# qo-100-digital-power-meter.net
KiCad netlist of a schematic drawn in EAGLE
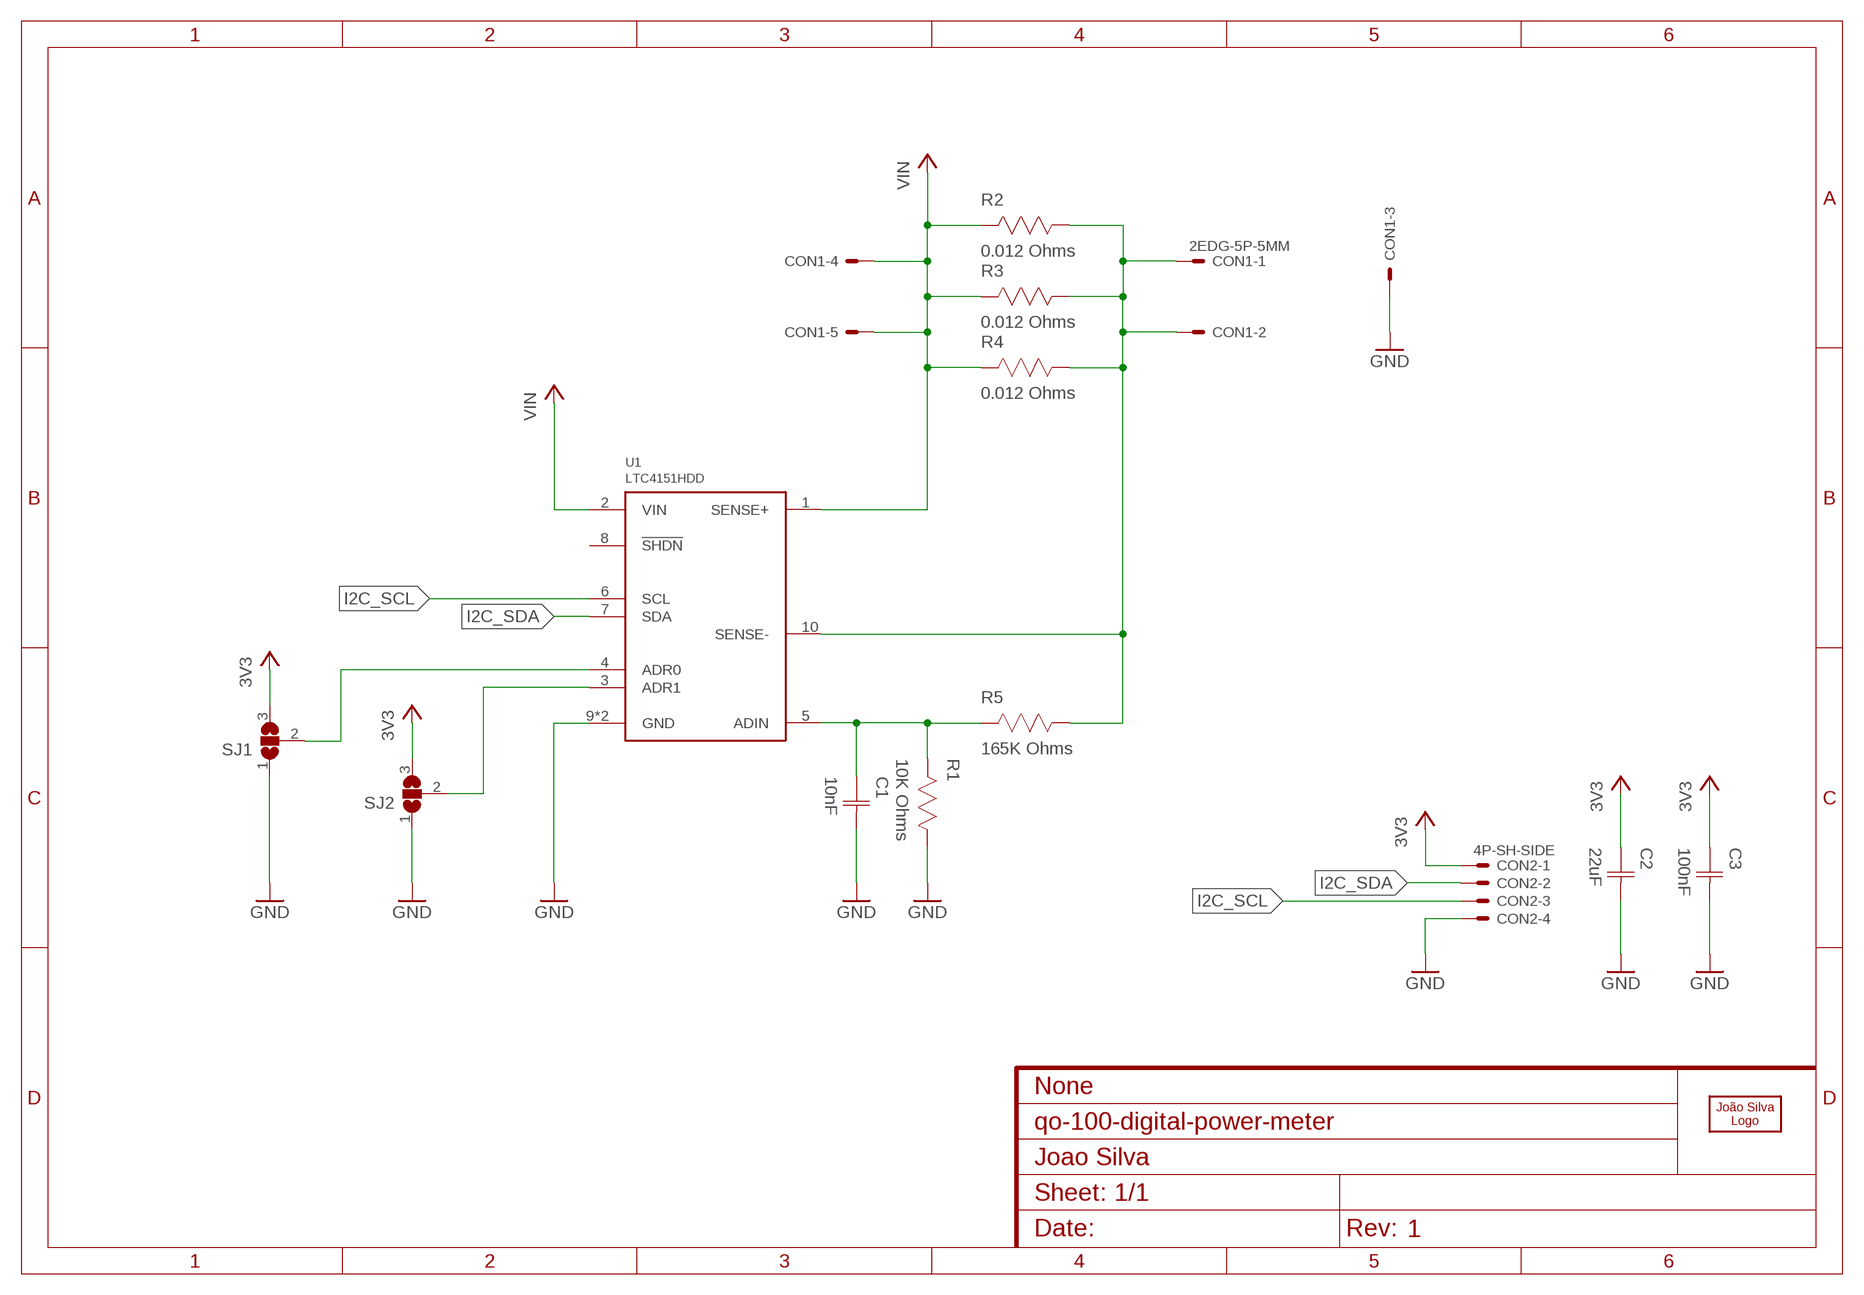
[diagram p0: schematic, sheet 1]

(export (version "E")
  (design (tool "Eeschema 10.0.6"))
  (components
    (comp (ref "C1")
      (value "10nF")
      (footprint "eagle-import:CAP0603")
      (libsource (lib "eagle-import") (part "CAPACITOR-0603"))
    )
    (comp (ref "C2")
      (value "22uF")
      (footprint "eagle-import:CAP1206")
      (libsource (lib "eagle-import") (part "CAPACITOR-1206"))
    )
    (comp (ref "C3")
      (value "100nF")
      (footprint "eagle-import:CAP0603")
      (libsource (lib "eagle-import") (part "CAPACITOR-0603"))
    )
    (comp (ref "CON1")
      (value "2EDG-5P-5MM")
      (footprint "eagle-import:2EDG-5P-5MM")
      (libsource (lib "eagle-import") (part "2EDG-5P-5MM"))
    )
    (comp (ref "CON2")
      (value "4P-SH-SIDE")
      (footprint "eagle-import:SH-04-SIDE")
      (libsource (lib "eagle-import") (part "4P-SH-SIDE"))
    )
    (comp (ref "LOGO1")
      (value "JS-5MM")
      (footprint "eagle-import:JS_5MM")
      (libsource (lib "eagle-import") (part "JS-5MM"))
    )
    (comp (ref "R1")
      (value "10K Ohms")
      (footprint "eagle-import:RES0603")
      (libsource (lib "eagle-import") (part "RESISTOR-0603"))
    )
    (comp (ref "R2")
      (value "0.012 Ohms")
      (footprint "eagle-import:RES2512")
      (libsource (lib "eagle-import") (part "RESISTOR-2512"))
    )
    (comp (ref "R3")
      (value "0.012 Ohms")
      (footprint "eagle-import:RES2512")
      (libsource (lib "eagle-import") (part "RESISTOR-2512"))
    )
    (comp (ref "R4")
      (value "0.012 Ohms")
      (footprint "eagle-import:RES2512")
      (libsource (lib "eagle-import") (part "RESISTOR-2512"))
    )
    (comp (ref "R5")
      (value "165K Ohms")
      (footprint "eagle-import:RES0603")
      (libsource (lib "eagle-import") (part "RESISTOR-0603"))
    )
    (comp (ref "SJ1")
      (value "SJ2S")
      (footprint "eagle-import:SJ2_S")
      (libsource (lib "eagle-import") (part "SJ2S"))
    )
    (comp (ref "SJ2")
      (value "SJ2S")
      (footprint "eagle-import:SJ2_S")
      (libsource (lib "eagle-import") (part "SJ2S"))
    )
    (comp (ref "U1")
      (value "LTC4151HDD")
      (footprint "eagle-import:DFN10")
      (libsource (lib "eagle-import") (part "LTC4151?DDH"))
    )
  )
  (nets
    (net (code "1") (name "3V3") (class "Default")
      (node (ref "C2") (pin "1") (pinfunction "C1_1") (pintype "passive"))
      (node (ref "C3") (pin "1") (pinfunction "C1_1") (pintype "passive"))
      (node (ref "CON2") (pin "1") (pinfunction "S_1") (pintype "passive"))
      (node (ref "SJ1") (pin "3") (pinfunction "3_3") (pintype "passive"))
      (node (ref "SJ2") (pin "3") (pinfunction "3_3") (pintype "passive"))
    )
    (net (code "2") (name "GND") (class "Default")
      (node (ref "C1") (pin "2") (pinfunction "C2_2") (pintype "passive"))
      (node (ref "C2") (pin "2") (pinfunction "C2_2") (pintype "passive"))
      (node (ref "C3") (pin "2") (pinfunction "C2_2") (pintype "passive"))
      (node (ref "CON1") (pin "P$3") (pinfunction "S_P$3") (pintype "passive"))
      (node (ref "CON2") (pin "4") (pinfunction "S_4") (pintype "passive"))
      (node (ref "R1") (pin "1") (pinfunction "1_1") (pintype "passive"))
      (node (ref "SJ1") (pin "1") (pinfunction "1_1") (pintype "passive"))
      (node (ref "SJ2") (pin "1") (pinfunction "1_1") (pintype "passive"))
      (node (ref "U1") (pin "11") (pinfunction "GND_11") (pintype "bidirectional"))
      (node (ref "U1") (pin "9") (pinfunction "GND_9") (pintype "bidirectional"))
    )
    (net (code "3") (name "I2C_SCL") (class "Default")
      (node (ref "CON2") (pin "3") (pinfunction "S_3") (pintype "passive"))
      (node (ref "U1") (pin "6") (pinfunction "SCL_6") (pintype "bidirectional"))
    )
    (net (code "4") (name "I2C_SDA") (class "Default")
      (node (ref "CON2") (pin "2") (pinfunction "S_2") (pintype "passive"))
      (node (ref "U1") (pin "7") (pinfunction "SDA_7") (pintype "bidirectional"))
    )
    (net (code "5") (name "Net-(C1-C1)") (class "Default")
      (node (ref "C1") (pin "1") (pinfunction "C1_1") (pintype "passive"))
      (node (ref "R1") (pin "2") (pinfunction "2_2") (pintype "passive"))
      (node (ref "R5") (pin "2") (pinfunction "2_2") (pintype "passive"))
      (node (ref "U1") (pin "5") (pinfunction "ADIN_5") (pintype "bidirectional"))
    )
    (net (code "6") (name "Net-(CON1A-S)") (class "Default")
      (node (ref "CON1") (pin "P$1") (pinfunction "S_P$1") (pintype "passive"))
      (node (ref "CON1") (pin "P$2") (pinfunction "S_P$2") (pintype "passive"))
      (node (ref "R2") (pin "1") (pinfunction "1_1") (pintype "passive"))
      (node (ref "R3") (pin "1") (pinfunction "1_1") (pintype "passive"))
      (node (ref "R4") (pin "1") (pinfunction "1_1") (pintype "passive"))
      (node (ref "R5") (pin "1") (pinfunction "1_1") (pintype "passive"))
      (node (ref "U1") (pin "10") (pinfunction "SENSE-_10") (pintype "bidirectional"))
    )
    (net (code "7") (name "Net-(U1-ADR0)") (class "Default")
      (node (ref "SJ1") (pin "2") (pinfunction "2_2") (pintype "passive"))
      (node (ref "U1") (pin "4") (pinfunction "ADR0_4") (pintype "bidirectional"))
    )
    (net (code "8") (name "Net-(U1-ADR1)") (class "Default")
      (node (ref "SJ2") (pin "2") (pinfunction "2_2") (pintype "passive"))
      (node (ref "U1") (pin "3") (pinfunction "ADR1_3") (pintype "bidirectional"))
    )
    (net (code "9") (name "VIN") (class "Default")
      (node (ref "CON1") (pin "P$4") (pinfunction "S_P$4") (pintype "passive"))
      (node (ref "CON1") (pin "P$5") (pinfunction "S_P$5") (pintype "passive"))
      (node (ref "R2") (pin "2") (pinfunction "2_2") (pintype "passive"))
      (node (ref "R3") (pin "2") (pinfunction "2_2") (pintype "passive"))
      (node (ref "R4") (pin "2") (pinfunction "2_2") (pintype "passive"))
      (node (ref "U1") (pin "1") (pinfunction "SENSE+_1") (pintype "bidirectional"))
      (node (ref "U1") (pin "2") (pinfunction "VIN_2") (pintype "bidirectional"))
    )
    (net (code "10") (name "unconnected-(U1-~{SHDN}-Pad8)") (class "Default")
      (node (ref "U1") (pin "8") (pinfunction "~{SHDN}_8") (pintype "bidirectional"))
    )
  )
)
